# variablePedal.net
KiCad netlist of a schematic drawn in EAGLE
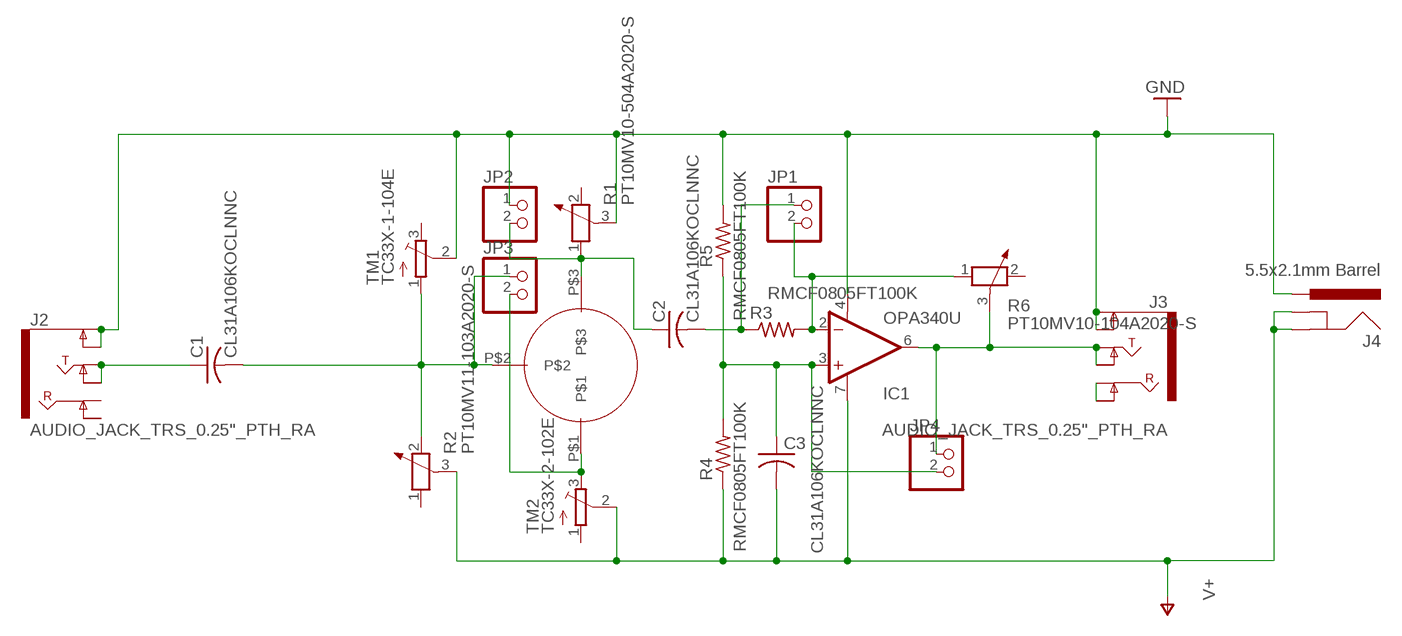
[diagram p0: schematic, sheet 1]

(export (version "E")
  (design (tool "Eeschema 10.0.6"))
  (components
    (comp (ref "C1")
      (value "CL31A106KOCLNNC")
      (footprint "eagle-import:C1206")
      (libsource (lib "eagle-import") (part "C-USC1206"))
    )
    (comp (ref "C2")
      (value "CL31A106KOCLNNC")
      (footprint "eagle-import:C1206")
      (libsource (lib "eagle-import") (part "C-USC1206"))
    )
    (comp (ref "C3")
      (value "CL31A106KOCLNNC")
      (footprint "eagle-import:C1206")
      (libsource (lib "eagle-import") (part "C-USC1206"))
    )
    (comp (ref "IC1")
      (value "OPA340U")
      (footprint "eagle-import:SO08")
      (fields (field (name "MPN") "OPA340UA"))
      (libsource (lib "eagle-import") (part "OPA340U"))
    )
    (comp (ref "J2")
      (value "AUDIO_JACK_TRS_0.25\"_PTH_RA")
      (footprint "eagle-import:AUDIO_JACK_0.25__TRS_PTH_RA")
      (libsource (lib "eagle-import") (part "AUDIO_JACK_TRS_0.25{dblquote}_PTH_RA"))
    )
    (comp (ref "J3")
      (value "AUDIO_JACK_TRS_0.25\"_PTH_RA")
      (footprint "eagle-import:AUDIO_JACK_0.25__TRS_PTH_RA")
      (libsource (lib "eagle-import") (part "AUDIO_JACK_TRS_0.25{dblquote}_PTH_RA"))
    )
    (comp (ref "J4")
      (value "5.5x2.1mm Barrel")
      (footprint "eagle-import:POWER_JACK_SMD")
      (libsource (lib "eagle-import") (part "POWER_JACKSMD"))
    )
    (comp (ref "JP1")
      (value "PINHD-1X2")
      (footprint "eagle-import:1X02")
      (libsource (lib "eagle-import") (part "PINHD-1X2"))
    )
    (comp (ref "JP2")
      (value "PINHD-1X2")
      (footprint "eagle-import:1X02")
      (libsource (lib "eagle-import") (part "PINHD-1X2"))
    )
    (comp (ref "JP3")
      (value "PINHD-1X2")
      (footprint "eagle-import:1X02")
      (libsource (lib "eagle-import") (part "PINHD-1X2"))
    )
    (comp (ref "JP4")
      (value "PINHD-1X2")
      (footprint "eagle-import:1X02")
      (libsource (lib "eagle-import") (part "PINHD-1X2"))
    )
    (comp (ref "R1")
      (value "PT10MV10-504A2020-S")
      (footprint "eagle-import:PT-10")
      (libsource (lib "eagle-import") (part "POTENTIOMETER_PT-10"))
    )
    (comp (ref "R2")
      (value "PT10MV11-103A2020-S")
      (footprint "eagle-import:PT-10")
      (libsource (lib "eagle-import") (part "POTENTIOMETER_PT-10"))
    )
    (comp (ref "R3")
      (value "RMCF0805FT100K")
      (footprint "eagle-import:R0805")
      (libsource (lib "eagle-import") (part "R-US_R0805"))
    )
    (comp (ref "R4")
      (value "RMCF0805FT100K")
      (footprint "eagle-import:R0805")
      (libsource (lib "eagle-import") (part "R-US_R0805"))
    )
    (comp (ref "R5")
      (value "RMCF0805FT100K")
      (footprint "eagle-import:R0805")
      (libsource (lib "eagle-import") (part "R-US_R0805"))
    )
    (comp (ref "R6")
      (value "PT10MV10-104A2020-S")
      (footprint "eagle-import:PT-10")
      (libsource (lib "eagle-import") (part "POTENTIOMETER_PT-10"))
    )
    (comp (ref "TM1")
      (value "TC33X-1-104E")
      (footprint "eagle-import:TC33X")
      (libsource (lib "eagle-import") (part "TRIMPOTTC33X"))
    )
    (comp (ref "TM2")
      (value "TC33X-2-102E")
      (footprint "eagle-import:TC33X")
      (libsource (lib "eagle-import") (part "TRIMPOTTC33X"))
    )
    (comp (ref "U$1")
      (value "917-43-103-41-005000")
      (footprint "eagle-import:TO-5")
      (libsource (lib "eagle-import") (part "917-43-103-41-005000"))
    )
  )
  (nets
    (net (code "1") (name "GND") (class "Default")
      (node (ref "IC1") (pin "4") (pinfunction "V-_4") (pintype "power_in"))
      (node (ref "J2") (pin "SLEEVE") (pinfunction "EARTH_SLEEVE") (pintype "bidirectional"))
      (node (ref "J2") (pin "SLEEVE-NORM") (pinfunction "EARTH-NORM_SLEEVE-NORM") (pintype "bidirectional"))
      (node (ref "J3") (pin "SLEEVE") (pinfunction "EARTH_SLEEVE") (pintype "bidirectional"))
      (node (ref "J3") (pin "SLEEVE-NORM") (pinfunction "EARTH-NORM_SLEEVE-NORM") (pintype "bidirectional"))
      (node (ref "J4") (pin "VIN0") (pinfunction "PWR_VIN0") (pintype "bidirectional"))
      (node (ref "JP2") (pin "1") (pinfunction "1_1") (pintype "passive"))
      (node (ref "R1") (pin "3") (pinfunction "3_3") (pintype "passive"))
      (node (ref "R5") (pin "2") (pinfunction "2_2") (pintype "passive"))
      (node (ref "TM1") (pin "2") (pinfunction "S_2") (pintype "passive"))
    )
    (net (code "2") (name "Net-(C1-Pad1)") (class "Default")
      (node (ref "C1") (pin "1") (pinfunction "1_1") (pintype "passive"))
      (node (ref "J2") (pin "TIP") (pinfunction "TIP_TIP") (pintype "bidirectional"))
      (node (ref "J2") (pin "TIP-NORM") (pinfunction "TIP-NORM_TIP-NORM") (pintype "bidirectional"))
    )
    (net (code "3") (name "Net-(C2-Pad1)") (class "Default")
      (node (ref "C2") (pin "1") (pinfunction "1_1") (pintype "passive"))
      (node (ref "JP2") (pin "2") (pinfunction "2_2") (pintype "passive"))
      (node (ref "R1") (pin "1") (pinfunction "1_1") (pintype "passive"))
      (node (ref "U$1") (pin "P$3") (pinfunction "P$3_P$3") (pintype "bidirectional"))
    )
    (net (code "4") (name "Net-(C2-Pad2)") (class "Default")
      (node (ref "C2") (pin "2") (pinfunction "2_2") (pintype "passive"))
      (node (ref "JP1") (pin "1") (pinfunction "1_1") (pintype "passive"))
      (node (ref "R3") (pin "1") (pinfunction "1_1") (pintype "passive"))
    )
    (net (code "5") (name "Net-(IC1-+IN)") (class "Default")
      (node (ref "C3") (pin "1") (pinfunction "1_1") (pintype "passive"))
      (node (ref "IC1") (pin "3") (pinfunction "+IN_3") (pintype "input"))
      (node (ref "JP4") (pin "2") (pinfunction "2_2") (pintype "passive"))
      (node (ref "R4") (pin "2") (pinfunction "2_2") (pintype "passive"))
      (node (ref "R5") (pin "1") (pinfunction "1_1") (pintype "passive"))
    )
    (net (code "6") (name "Net-(IC1--IN)") (class "Default")
      (node (ref "IC1") (pin "2") (pinfunction "-IN_2") (pintype "input"))
      (node (ref "JP1") (pin "2") (pinfunction "2_2") (pintype "passive"))
      (node (ref "R3") (pin "2") (pinfunction "2_2") (pintype "passive"))
      (node (ref "R6") (pin "1") (pinfunction "1_1") (pintype "passive"))
    )
    (net (code "7") (name "Net-(IC1-OUT)") (class "Default")
      (node (ref "IC1") (pin "6") (pinfunction "OUT_6") (pintype "output"))
      (node (ref "J3") (pin "TIP") (pinfunction "TIP_TIP") (pintype "bidirectional"))
      (node (ref "J3") (pin "TIP-NORM") (pinfunction "TIP-NORM_TIP-NORM") (pintype "bidirectional"))
      (node (ref "JP4") (pin "1") (pinfunction "1_1") (pintype "passive"))
      (node (ref "R6") (pin "3") (pinfunction "3_3") (pintype "passive"))
    )
    (net (code "8") (name "Net-(J3-PadRING)") (class "Default")
      (node (ref "J3") (pin "RING") (pinfunction "RING_RING") (pintype "bidirectional"))
      (node (ref "J3") (pin "RING-NORM") (pinfunction "RING-NORM_RING-NORM") (pintype "bidirectional"))
    )
    (net (code "9") (name "Net-(TM1-A)") (class "Default")
      (node (ref "C1") (pin "2") (pinfunction "2_2") (pintype "passive"))
      (node (ref "JP3") (pin "1") (pinfunction "1_1") (pintype "passive"))
      (node (ref "R2") (pin "2") (pinfunction "2_2") (pintype "passive"))
      (node (ref "TM1") (pin "1") (pinfunction "A_1") (pintype "passive"))
      (node (ref "U$1") (pin "P$2") (pinfunction "P$2_P$2") (pintype "bidirectional"))
    )
    (net (code "10") (name "Net-(TM2-E)") (class "Default")
      (node (ref "JP3") (pin "2") (pinfunction "2_2") (pintype "passive"))
      (node (ref "TM2") (pin "3") (pinfunction "E_3") (pintype "passive"))
      (node (ref "U$1") (pin "P$1") (pinfunction "P$1_P$1") (pintype "bidirectional"))
    )
    (net (code "11") (name "V+") (class "Default")
      (node (ref "C3") (pin "2") (pinfunction "2_2") (pintype "passive"))
      (node (ref "IC1") (pin "7") (pinfunction "V+_7") (pintype "power_in"))
      (node (ref "J4") (pin "GND") (pinfunction "GNDBREAK_GND") (pintype "bidirectional"))
      (node (ref "J4") (pin "P$4") (pinfunction "GND_P$4") (pintype "bidirectional"))
      (node (ref "R2") (pin "3") (pinfunction "3_3") (pintype "passive"))
      (node (ref "R4") (pin "1") (pinfunction "1_1") (pintype "passive"))
      (node (ref "TM2") (pin "2") (pinfunction "S_2") (pintype "passive"))
    )
    (net (code "12") (name "unconnected-(J2-PadRING)") (class "Default")
      (node (ref "J2") (pin "RING") (pinfunction "RING_RING") (pintype "bidirectional"))
    )
    (net (code "13") (name "unconnected-(J2-PadRING-NORM)") (class "Default")
      (node (ref "J2") (pin "RING-NORM") (pinfunction "RING-NORM_RING-NORM") (pintype "bidirectional"))
    )
    (net (code "14") (name "unconnected-(R1-Pad2)") (class "Default")
      (node (ref "R1") (pin "2") (pinfunction "2_2") (pintype "passive"))
    )
    (net (code "15") (name "unconnected-(R2-Pad1)") (class "Default")
      (node (ref "R2") (pin "1") (pinfunction "1_1") (pintype "passive"))
    )
    (net (code "16") (name "unconnected-(R6-Pad2)") (class "Default")
      (node (ref "R6") (pin "2") (pinfunction "2_2") (pintype "passive"))
    )
    (net (code "17") (name "unconnected-(TM1-E-Pad3)") (class "Default")
      (node (ref "TM1") (pin "3") (pinfunction "E_3") (pintype "passive"))
    )
    (net (code "18") (name "unconnected-(TM2-A-Pad1)") (class "Default")
      (node (ref "TM2") (pin "1") (pinfunction "A_1") (pintype "passive"))
    )
  )
)
